# 1Wire.net
KiCad netlist of a schematic drawn in Altium Designer
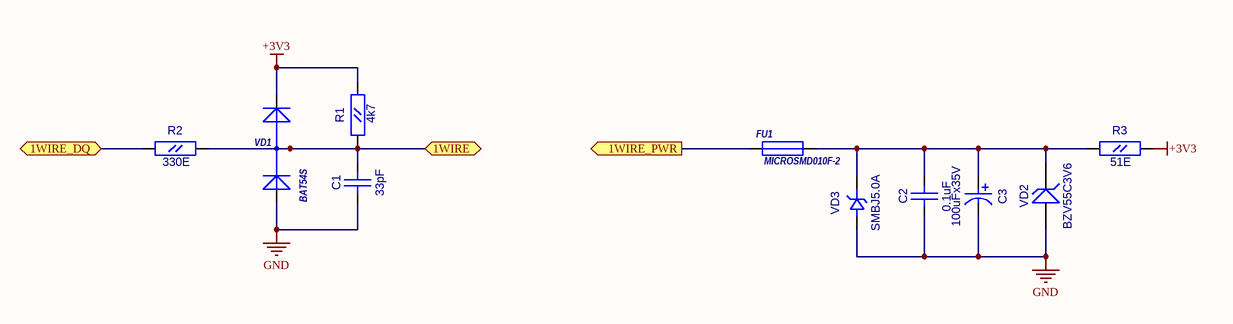
[diagram p0: 1Wire.SchDoc]

(export (version "E")
  (design (tool "Eeschema 10.0.6"))
  (components
    (comp (ref "C1")
      (value "33pF")
      (footprint "CC0603")
      (description "CC0603")
      (libsource (lib "gprs_modem_2") (part "CC0603"))
    )
    (comp (ref "C2")
      (value "0.1uF")
      (footprint "CC0603")
      (description "CC0603")
      (libsource (lib "gprs_modem_2") (part "CC0603"))
    )
    (comp (ref "C3")
      (value "100uFx35V")
      (footprint "CC20X2.54")
      (description "CAP0.25")
      (libsource (lib "gprs_modem_2") (part "CAP0.25"))
    )
    (comp (ref "FU1")
      (value "MICROSMD010F-2")
      (footprint "RC1210")
      (description "MICROSMD")
      (libsource (lib "gprs_modem_2") (part "MICROSMD"))
    )
    (comp (ref "R1")
      (value "4k7")
      (footprint "RC0603")
      (description "RC0603")
      (libsource (lib "gprs_modem_2") (part "RC0603"))
    )
    (comp (ref "R2")
      (value "330E")
      (footprint "RC0603")
      (description "RC0603")
      (libsource (lib "gprs_modem_2") (part "RC0603"))
    )
    (comp (ref "R3")
      (value "51E")
      (footprint "RC0603")
      (description "RC0603")
      (libsource (lib "gprs_modem_2") (part "RC0603"))
    )
    (comp (ref "VD1")
      (value "BAT54S")
      (footprint "SOT-23(GSD)")
      (description "1.0 Ampere General Purpose Rectifier")
      (libsource (lib "gprs_modem_2") (part "BAT54S"))
    )
    (comp (ref "VD2")
      (value "BZV55C3V6")
      (footprint "SOD-80")
      (description "Zener Voltage Regulator Diode")
      (libsource (lib "gprs_modem_2") (part "BZV55C5V1"))
    )
    (comp (ref "VD3")
      (value "SMBJ5.0A")
      (footprint "SMB")
      (description "SMBJ")
      (libsource (lib "gprs_modem_2") (part "SMBJ"))
    )
  )
  (nets
    (net (code "1") (name "+3V3") (class "Default")
      (node (ref "R1") (pin "2") (pinfunction "B_2") (pintype "passive"))
      (node (ref "R3") (pin "2") (pinfunction "B_2") (pintype "passive"))
      (node (ref "VD1") (pin "2") (pinfunction "K_2") (pintype "passive"))
    )
    (net (code "2") (name "/1WIRE") (class "Default")
      (node (ref "C1") (pin "2") (pinfunction "B_2") (pintype "passive"))
      (node (ref "R1") (pin "1") (pinfunction "A_1") (pintype "passive"))
      (node (ref "R2") (pin "2") (pinfunction "B_2") (pintype "passive"))
      (node (ref "VD1") (pin "3") (pinfunction "AK_3") (pintype "passive"))
    )
    (net (code "3") (name "/1WIRE_DQ") (class "Default")
      (node (ref "R2") (pin "1") (pinfunction "A_1") (pintype "passive"))
    )
    (net (code "4") (name "/1WIRE_PWR") (class "Default") (node (ref "FU1") (pin "1") (pintype "passive")))
    (net (code "5") (name "GND") (class "Default")
      (node (ref "C1") (pin "1") (pinfunction "A_1") (pintype "passive"))
      (node (ref "C2") (pin "1") (pinfunction "A_1") (pintype "passive"))
      (node (ref "C3") (pin "2") (pinfunction "minus_2") (pintype "passive"))
      (node (ref "VD1") (pin "1") (pinfunction "A_1") (pintype "passive"))
      (node (ref "VD2") (pin "1") (pinfunction "A_1") (pintype "passive"))
      (node (ref "VD3") (pin "1") (pinfunction "A_1") (pintype "passive"))
    )
    (net (code "6") (name "Net-(C2-B)") (class "Default")
      (node (ref "C2") (pin "2") (pinfunction "B_2") (pintype "passive"))
      (node (ref "C3") (pin "1") (pinfunction "plus_1") (pintype "passive"))
      (node (ref "FU1") (pin "2") (pintype "passive"))
      (node (ref "R3") (pin "1") (pinfunction "A_1") (pintype "passive"))
      (node (ref "VD2") (pin "2") (pintype "passive"))
      (node (ref "VD3") (pin "2") (pinfunction "K_2") (pintype "passive"))
    )
  )
)
